# gasz_hler.net
KiCad netlist of a schematic drawn in EAGLE
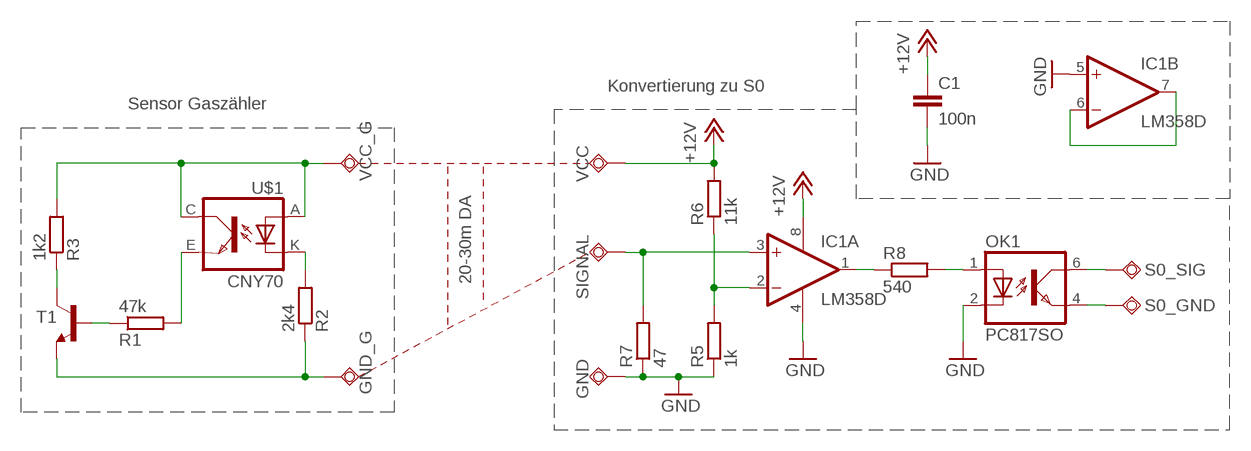
[diagram p0: schematic, sheet 1]

(export (version "E")
  (design (tool "Eeschema 10.0.6"))
  (components
    (comp (ref "C1")
      (value "100n")
      (footprint "eagle-import:C0805")
      (libsource (lib "eagle-import") (part "C-EUC0805"))
    )
    (comp (ref "GND")
      (value "TPSQTP20SQ")
      (footprint "eagle-import:TP20SQ")
      (libsource (lib "eagle-import") (part "TPSQTP20SQ"))
    )
    (comp (ref "GND_G")
      (value "TPSQTP20SQ")
      (footprint "eagle-import:TP20SQ")
      (libsource (lib "eagle-import") (part "TPSQTP20SQ"))
    )
    (comp (ref "IC1")
      (value "LM358D")
      (footprint "eagle-import:SO08")
      (libsource (lib "eagle-import") (part "LM358D"))
    )
    (comp (ref "OK1")
      (value "PC817SO")
      (footprint "eagle-import:SO4")
      (libsource (lib "eagle-import") (part "PC817SO"))
    )
    (comp (ref "R1")
      (value "47k")
      (footprint "eagle-import:R0805")
      (libsource (lib "eagle-import") (part "R-EU_R0805"))
    )
    (comp (ref "R2")
      (value "2k4")
      (footprint "eagle-import:R0805")
      (libsource (lib "eagle-import") (part "R-EU_R0805"))
    )
    (comp (ref "R3")
      (value "1k2")
      (footprint "eagle-import:R0805")
      (libsource (lib "eagle-import") (part "R-EU_R0805"))
    )
    (comp (ref "R5")
      (value "1k")
      (footprint "eagle-import:M0805")
      (libsource (lib "eagle-import") (part "R-EU_M0805"))
    )
    (comp (ref "R6")
      (value "11k")
      (footprint "eagle-import:M0805")
      (libsource (lib "eagle-import") (part "R-EU_M0805"))
    )
    (comp (ref "R7")
      (value "47")
      (footprint "eagle-import:M0805")
      (libsource (lib "eagle-import") (part "R-EU_M0805"))
    )
    (comp (ref "R8")
      (value "540")
      (footprint "eagle-import:M0805")
      (libsource (lib "eagle-import") (part "R-EU_M0805"))
    )
    (comp (ref "S0_GND")
      (value "TPSQTP20SQ")
      (footprint "eagle-import:TP20SQ")
      (libsource (lib "eagle-import") (part "TPSQTP20SQ"))
    )
    (comp (ref "S0_SIG")
      (value "TPSQTP20SQ")
      (footprint "eagle-import:TP20SQ")
      (libsource (lib "eagle-import") (part "TPSQTP20SQ"))
    )
    (comp (ref "SIGNAL")
      (value "TPSQTP20SQ")
      (footprint "eagle-import:TP20SQ")
      (libsource (lib "eagle-import") (part "TPSQTP20SQ"))
    )
    (comp (ref "T1")
      (value "-NPN-SOT23-EBC")
      (footprint "eagle-import:SOT23-EBC")
      (libsource (lib "eagle-import") (part "-NPN-SOT23-EBC"))
    )
    (comp (ref "U$1")
      (value "CNY70")
      (footprint "eagle-import:4")
      (libsource (lib "eagle-import") (part "CNY70"))
    )
    (comp (ref "VCC")
      (value "TPSQTP20SQ")
      (footprint "eagle-import:TP20SQ")
      (libsource (lib "eagle-import") (part "TPSQTP20SQ"))
    )
    (comp (ref "VCC_G")
      (value "TPSQTP20SQ")
      (footprint "eagle-import:TP20SQ")
      (libsource (lib "eagle-import") (part "TPSQTP20SQ"))
    )
  )
  (nets
    (net (code "1") (name "+12V") (class "Default")
      (node (ref "C1") (pin "1") (pinfunction "1_1") (pintype "passive"))
      (node (ref "IC1") (pin "8") (pinfunction "V+_8") (pintype "power_in"))
      (node (ref "R6") (pin "2") (pinfunction "2_2") (pintype "passive"))
      (node (ref "VCC") (pin "TP") (pinfunction "TP_TP") (pintype "input"))
    )
    (net (code "2") (name "GND") (class "Default")
      (node (ref "C1") (pin "2") (pinfunction "2_2") (pintype "passive"))
      (node (ref "GND") (pin "TP") (pinfunction "TP_TP") (pintype "input"))
      (node (ref "IC1") (pin "4") (pinfunction "V-_4") (pintype "power_in"))
      (node (ref "IC1") (pin "5") (pinfunction "+IN_5") (pintype "input"))
      (node (ref "OK1") (pin "2") (pinfunction "C_2") (pintype "passive"))
      (node (ref "R5") (pin "1") (pinfunction "1_1") (pintype "passive"))
      (node (ref "R7") (pin "1") (pinfunction "1_1") (pintype "passive"))
    )
    (net (code "3") (name "Net-(GND_G-PadTP)") (class "Default")
      (node (ref "GND_G") (pin "TP") (pinfunction "TP_TP") (pintype "input"))
      (node (ref "R2") (pin "1") (pinfunction "1_1") (pintype "passive"))
      (node (ref "T1") (pin "E") (pinfunction "E_E") (pintype "passive"))
    )
    (net (code "4") (name "Net-(IC1A-+IN)") (class "Default")
      (node (ref "IC1") (pin "3") (pinfunction "+IN_3") (pintype "input"))
      (node (ref "R7") (pin "2") (pinfunction "2_2") (pintype "passive"))
      (node (ref "SIGNAL") (pin "TP") (pinfunction "TP_TP") (pintype "input"))
    )
    (net (code "5") (name "Net-(IC1A--IN)") (class "Default")
      (node (ref "IC1") (pin "2") (pinfunction "-IN_2") (pintype "input"))
      (node (ref "R5") (pin "2") (pinfunction "2_2") (pintype "passive"))
      (node (ref "R6") (pin "1") (pinfunction "1_1") (pintype "passive"))
    )
    (net (code "6") (name "Net-(IC1A-OUT)") (class "Default")
      (node (ref "IC1") (pin "1") (pinfunction "OUT_1") (pintype "output"))
      (node (ref "R8") (pin "1") (pinfunction "1_1") (pintype "passive"))
    )
    (net (code "7") (name "Net-(IC1B--IN)") (class "Default")
      (node (ref "IC1") (pin "6") (pinfunction "-IN_6") (pintype "input"))
      (node (ref "IC1") (pin "7") (pinfunction "OUT_7") (pintype "output"))
    )
    (net (code "8") (name "Net-(OK1-A)") (class "Default")
      (node (ref "OK1") (pin "1") (pinfunction "A_1") (pintype "passive"))
      (node (ref "R8") (pin "2") (pinfunction "2_2") (pintype "passive"))
    )
    (net (code "9") (name "Net-(OK1-COL)") (class "Default")
      (node (ref "OK1") (pin "6") (pinfunction "COL_6") (pintype "passive"))
      (node (ref "S0_SIG") (pin "TP") (pinfunction "TP_TP") (pintype "input"))
    )
    (net (code "10") (name "Net-(OK1-EMIT)") (class "Default")
      (node (ref "OK1") (pin "4") (pinfunction "EMIT_4") (pintype "passive"))
      (node (ref "S0_GND") (pin "TP") (pinfunction "TP_TP") (pintype "input"))
    )
    (net (code "11") (name "Net-(R1-Pad1)") (class "Default")
      (node (ref "R1") (pin "1") (pinfunction "1_1") (pintype "passive"))
      (node (ref "T1") (pin "B") (pinfunction "B_B") (pintype "passive"))
    )
    (net (code "12") (name "Net-(R3-Pad1)") (class "Default")
      (node (ref "R3") (pin "1") (pinfunction "1_1") (pintype "passive"))
      (node (ref "T1") (pin "C") (pinfunction "C_C") (pintype "passive"))
    )
    (net (code "13") (name "Net-(U$1-C)") (class "Default")
      (node (ref "R2") (pin "2") (pinfunction "2_2") (pintype "passive"))
      (node (ref "U$1") (pin "K") (pinfunction "C_K") (pintype "passive"))
    )
    (net (code "14") (name "Net-(U$1-COL)") (class "Default")
      (node (ref "R3") (pin "2") (pinfunction "2_2") (pintype "passive"))
      (node (ref "U$1") (pin "A") (pinfunction "A_A") (pintype "passive"))
      (node (ref "U$1") (pin "C") (pinfunction "COL_C") (pintype "passive"))
      (node (ref "VCC_G") (pin "TP") (pinfunction "TP_TP") (pintype "input"))
    )
    (net (code "15") (name "Net-(U$1-EMI)") (class "Default")
      (node (ref "R1") (pin "2") (pinfunction "2_2") (pintype "passive"))
      (node (ref "U$1") (pin "E") (pinfunction "EMI_E") (pintype "passive"))
    )
  )
)
